# Sheet1.net
KiCad netlist of a schematic drawn in Altium Designer
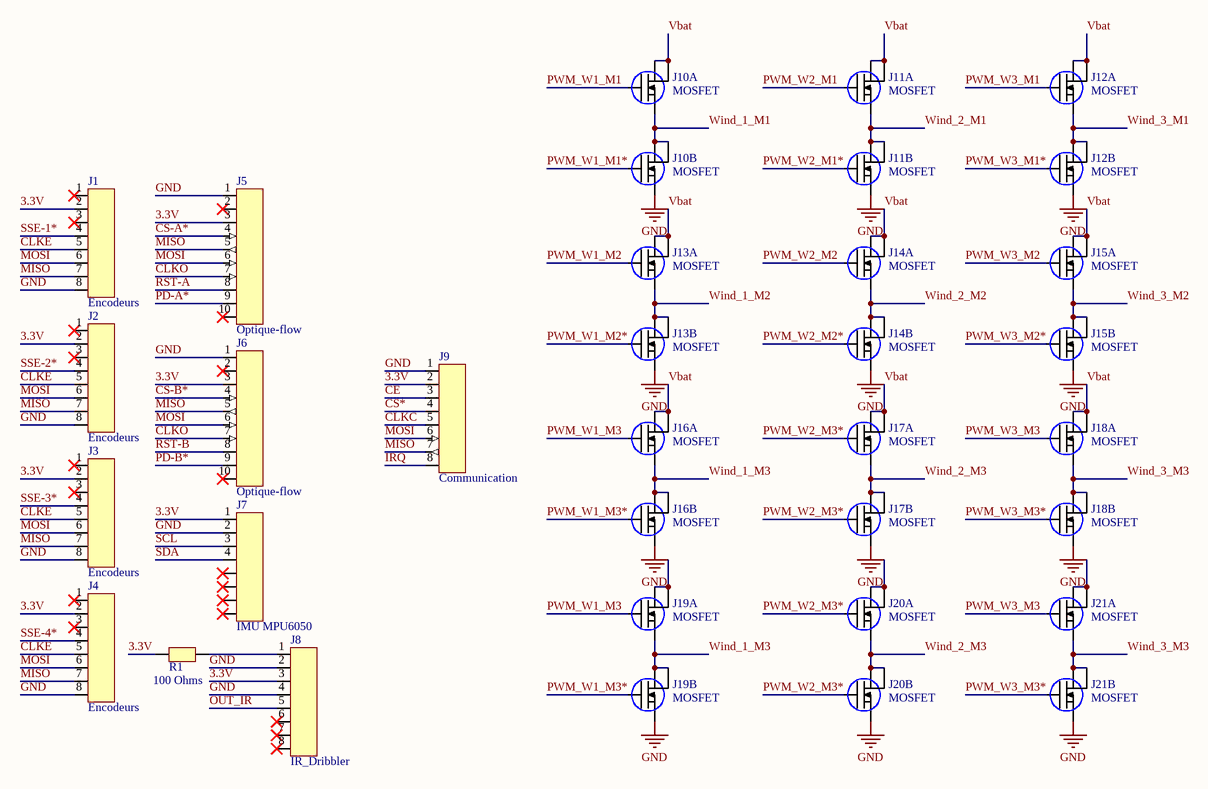
[diagram p0: Sheet1.SchDoc]

(export (version "E")
  (design (tool "Eeschema 10.0.6"))
  (components
    (comp (ref "J1")
      (value "Encodeurs")
      (footprint "Encodeur/IMU")
      (description "AS5048A")
      (libsource (lib "Schlib1") (part "Encodeurs"))
    )
    (comp (ref "J2")
      (value "Encodeurs")
      (footprint "Encodeur/IMU")
      (description "AS5048A")
      (libsource (lib "Schlib1") (part "Encodeurs"))
    )
    (comp (ref "J3")
      (value "Encodeurs")
      (footprint "Encodeur/IMU")
      (description "AS5048A")
      (libsource (lib "Schlib1") (part "Encodeurs"))
    )
    (comp (ref "J4")
      (value "Encodeurs")
      (footprint "Encodeur/IMU")
      (description "AS5048A")
      (libsource (lib "Schlib1") (part "Encodeurs"))
    )
    (comp (ref "J5")
      (value "Optique-flow")
      (footprint "IR_optique")
      (description "ADNS3080")
      (libsource (lib "Schlib1") (part "Optique-flow"))
    )
    (comp (ref "J6")
      (value "Optique-flow")
      (footprint "IR_optique")
      (description "ADNS3080")
      (libsource (lib "Schlib1") (part "Optique-flow"))
    )
    (comp (ref "J7")
      (value "IMU MPU6050")
      (footprint "Encodeur/IMU")
      (description "MPU6050 IMU")
      (libsource (lib "Schlib1") (part "IMU MPU6050"))
    )
    (comp (ref "J8")
      (value "IR_Dribbler")
      (footprint "Encodeur/IMU")
      (description "AS5048A")
      (libsource (lib "Schlib1") (part "Encodeurs"))
    )
    (comp (ref "J9")
      (value "Communication")
      (footprint "Comm nRF24L01")
      (description "Communication radio")
      (libsource (lib "Schlib1") (part "Communication"))
    )
    (comp (ref "J10")
      (value "MOSFET")
      (footprint "MOSFET")
      (description "MOSFET ESC IRF7910 10 A")
      (libsource (lib "Schlib1") (part "MOSFET"))
    )
    (comp (ref "J11")
      (value "MOSFET")
      (footprint "MOSFET")
      (description "MOSFET ESC IRF7910 10 A")
      (libsource (lib "Schlib1") (part "MOSFET"))
    )
    (comp (ref "J12")
      (value "MOSFET")
      (footprint "MOSFET")
      (description "MOSFET ESC IRF7910 10 A")
      (libsource (lib "Schlib1") (part "MOSFET"))
    )
    (comp (ref "J13")
      (value "MOSFET")
      (footprint "MOSFET")
      (description "MOSFET ESC IRF7910 10 A")
      (libsource (lib "Schlib1") (part "MOSFET"))
    )
    (comp (ref "J14")
      (value "MOSFET")
      (footprint "MOSFET")
      (description "MOSFET ESC IRF7910 10 A")
      (libsource (lib "Schlib1") (part "MOSFET"))
    )
    (comp (ref "J15")
      (value "MOSFET")
      (footprint "MOSFET")
      (description "MOSFET ESC IRF7910 10 A")
      (libsource (lib "Schlib1") (part "MOSFET"))
    )
    (comp (ref "J16")
      (value "MOSFET")
      (footprint "MOSFET")
      (description "MOSFET ESC IRF7910 10 A")
      (libsource (lib "Schlib1") (part "MOSFET"))
    )
    (comp (ref "J17")
      (value "MOSFET")
      (footprint "MOSFET")
      (description "MOSFET ESC IRF7910 10 A")
      (libsource (lib "Schlib1") (part "MOSFET"))
    )
    (comp (ref "J18")
      (value "MOSFET")
      (footprint "MOSFET")
      (description "MOSFET ESC IRF7910 10 A")
      (libsource (lib "Schlib1") (part "MOSFET"))
    )
    (comp (ref "J19")
      (value "MOSFET")
      (footprint "MOSFET")
      (description "MOSFET ESC IRF7910 10 A")
      (libsource (lib "Schlib1") (part "MOSFET"))
    )
    (comp (ref "J20")
      (value "MOSFET")
      (footprint "MOSFET")
      (description "MOSFET ESC IRF7910 10 A")
      (libsource (lib "Schlib1") (part "MOSFET"))
    )
    (comp (ref "J21")
      (value "MOSFET")
      (footprint "MOSFET")
      (description "MOSFET ESC IRF7910 10 A")
      (libsource (lib "Schlib1") (part "MOSFET"))
    )
    (comp (ref "R1")
      (value "Resistance")
      (footprint "empreinte 1206")
      (fields (field (name "100 OHMS") "100 Ohms"))
      (libsource (lib "Schlib1") (part "Resistance"))
    )
  )
  (nets
    (net (code "1") (name "/3.3V") (class "Default")
      (node (ref "J1") (pin "2") (pinfunction "2_2") (pintype "power_in"))
      (node (ref "J2") (pin "2") (pinfunction "2_2") (pintype "power_in"))
      (node (ref "J3") (pin "2") (pinfunction "2_2") (pintype "power_in"))
      (node (ref "J4") (pin "2") (pinfunction "2_2") (pintype "power_in"))
      (node (ref "J5") (pin "3") (pinfunction "3_3") (pintype "power_in"))
      (node (ref "J6") (pin "3") (pinfunction "3_3") (pintype "power_in"))
      (node (ref "J7") (pin "1") (pinfunction "1_1") (pintype "power_in"))
      (node (ref "J8") (pin "3") (pinfunction "3_3") (pintype "passive"))
      (node (ref "J9") (pin "2") (pinfunction "2_2") (pintype "power_in"))
      (node (ref "R1") (pin "1") (pinfunction "1_1") (pintype "passive"))
    )
    (net (code "2") (name "/CE") (class "Default")
      (node (ref "J9") (pin "3") (pinfunction "3_3") (pintype "passive"))
    )
    (net (code "3") (name "/CLKC") (class "Default")
      (node (ref "J9") (pin "5") (pinfunction "5_5") (pintype "passive"))
    )
    (net (code "4") (name "/CLKE") (class "Default")
      (node (ref "J1") (pin "5") (pinfunction "5_5") (pintype "passive"))
      (node (ref "J2") (pin "5") (pinfunction "5_5") (pintype "passive"))
      (node (ref "J3") (pin "5") (pinfunction "5_5") (pintype "passive"))
      (node (ref "J4") (pin "5") (pinfunction "5_5") (pintype "passive"))
    )
    (net (code "5") (name "/CLKO") (class "Default")
      (node (ref "J5") (pin "7") (pinfunction "7_7") (pintype "input"))
      (node (ref "J6") (pin "7") (pinfunction "7_7") (pintype "input"))
    )
    (net (code "6") (name "/CS*") (class "Default")
      (node (ref "J9") (pin "4") (pinfunction "4_4") (pintype "passive"))
    )
    (net (code "7") (name "/CS-A*") (class "Default")
      (node (ref "J5") (pin "4") (pinfunction "4_4") (pintype "input"))
    )
    (net (code "8") (name "/CS-B*") (class "Default")
      (node (ref "J6") (pin "4") (pinfunction "4_4") (pintype "input"))
    )
    (net (code "9") (name "/IRQ") (class "Default")
      (node (ref "J9") (pin "8") (pinfunction "8_8") (pintype "passive"))
    )
    (net (code "10") (name "/MISO") (class "Default")
      (node (ref "J1") (pin "7") (pinfunction "7_7") (pintype "passive"))
      (node (ref "J2") (pin "7") (pinfunction "7_7") (pintype "passive"))
      (node (ref "J3") (pin "7") (pinfunction "7_7") (pintype "passive"))
      (node (ref "J4") (pin "7") (pinfunction "7_7") (pintype "passive"))
      (node (ref "J5") (pin "5") (pinfunction "5_5") (pintype "output"))
      (node (ref "J6") (pin "5") (pinfunction "5_5") (pintype "output"))
      (node (ref "J9") (pin "7") (pinfunction "7_7") (pintype "output"))
    )
    (net (code "11") (name "/MOSI") (class "Default")
      (node (ref "J1") (pin "6") (pinfunction "6_6") (pintype "passive"))
      (node (ref "J2") (pin "6") (pinfunction "6_6") (pintype "passive"))
      (node (ref "J3") (pin "6") (pinfunction "6_6") (pintype "passive"))
      (node (ref "J4") (pin "6") (pinfunction "6_6") (pintype "passive"))
      (node (ref "J5") (pin "6") (pinfunction "6_6") (pintype "input"))
      (node (ref "J6") (pin "6") (pinfunction "6_6") (pintype "input"))
      (node (ref "J9") (pin "6") (pinfunction "6_6") (pintype "input"))
    )
    (net (code "12") (name "/OUT_IR") (class "Default")
      (node (ref "J8") (pin "5") (pinfunction "5_5") (pintype "passive"))
    )
    (net (code "13") (name "/PD-A*") (class "Default")
      (node (ref "J5") (pin "9") (pinfunction "9_9") (pintype "passive"))
    )
    (net (code "14") (name "/PD-B*") (class "Default")
      (node (ref "J6") (pin "9") (pinfunction "9_9") (pintype "passive"))
    )
    (net (code "15") (name "/PWM_W1_M1") (class "Default")
      (node (ref "J10") (pin "2") (pinfunction "2_2") (pintype "passive"))
    )
    (net (code "16") (name "/PWM_W1_M1*") (class "Default")
      (node (ref "J10") (pin "4") (pinfunction "4_4") (pintype "passive"))
    )
    (net (code "17") (name "/PWM_W1_M2") (class "Default")
      (node (ref "J13") (pin "2") (pinfunction "2_2") (pintype "passive"))
    )
    (net (code "18") (name "/PWM_W1_M2*") (class "Default")
      (node (ref "J13") (pin "4") (pinfunction "4_4") (pintype "passive"))
    )
    (net (code "19") (name "/PWM_W1_M3") (class "Default")
      (node (ref "J16") (pin "2") (pinfunction "2_2") (pintype "passive"))
      (node (ref "J19") (pin "2") (pinfunction "2_2") (pintype "passive"))
    )
    (net (code "20") (name "/PWM_W1_M3*") (class "Default")
      (node (ref "J16") (pin "4") (pinfunction "4_4") (pintype "passive"))
      (node (ref "J19") (pin "4") (pinfunction "4_4") (pintype "passive"))
    )
    (net (code "21") (name "/PWM_W2_M1") (class "Default")
      (node (ref "J11") (pin "2") (pinfunction "2_2") (pintype "passive"))
    )
    (net (code "22") (name "/PWM_W2_M1*") (class "Default")
      (node (ref "J11") (pin "4") (pinfunction "4_4") (pintype "passive"))
    )
    (net (code "23") (name "/PWM_W2_M2") (class "Default")
      (node (ref "J14") (pin "2") (pinfunction "2_2") (pintype "passive"))
    )
    (net (code "24") (name "/PWM_W2_M2*") (class "Default")
      (node (ref "J14") (pin "4") (pinfunction "4_4") (pintype "passive"))
    )
    (net (code "25") (name "/PWM_W2_M3*") (class "Default")
      (node (ref "J17") (pin "2") (pinfunction "2_2") (pintype "passive"))
      (node (ref "J17") (pin "4") (pinfunction "4_4") (pintype "passive"))
      (node (ref "J20") (pin "2") (pinfunction "2_2") (pintype "passive"))
      (node (ref "J20") (pin "4") (pinfunction "4_4") (pintype "passive"))
    )
    (net (code "26") (name "/PWM_W3_M1") (class "Default")
      (node (ref "J12") (pin "2") (pinfunction "2_2") (pintype "passive"))
    )
    (net (code "27") (name "/PWM_W3_M1*") (class "Default")
      (node (ref "J12") (pin "4") (pinfunction "4_4") (pintype "passive"))
    )
    (net (code "28") (name "/PWM_W3_M2") (class "Default")
      (node (ref "J15") (pin "2") (pinfunction "2_2") (pintype "passive"))
    )
    (net (code "29") (name "/PWM_W3_M2*") (class "Default")
      (node (ref "J15") (pin "4") (pinfunction "4_4") (pintype "passive"))
    )
    (net (code "30") (name "/PWM_W3_M3") (class "Default")
      (node (ref "J18") (pin "2") (pinfunction "2_2") (pintype "passive"))
      (node (ref "J21") (pin "2") (pinfunction "2_2") (pintype "passive"))
    )
    (net (code "31") (name "/PWM_W3_M3*") (class "Default")
      (node (ref "J18") (pin "4") (pinfunction "4_4") (pintype "passive"))
      (node (ref "J21") (pin "4") (pinfunction "4_4") (pintype "passive"))
    )
    (net (code "32") (name "/RST-A") (class "Default")
      (node (ref "J5") (pin "8") (pinfunction "8_8") (pintype "passive"))
    )
    (net (code "33") (name "/RST-B") (class "Default")
      (node (ref "J6") (pin "8") (pinfunction "8_8") (pintype "passive"))
    )
    (net (code "34") (name "/SCL") (class "Default")
      (node (ref "J7") (pin "3") (pinfunction "3_3") (pintype "passive"))
    )
    (net (code "35") (name "/SDA") (class "Default")
      (node (ref "J7") (pin "4") (pinfunction "4_4") (pintype "bidirectional"))
    )
    (net (code "36") (name "/SSE-1*") (class "Default")
      (node (ref "J1") (pin "4") (pinfunction "4_4") (pintype "passive"))
    )
    (net (code "37") (name "/SSE-2*") (class "Default")
      (node (ref "J2") (pin "4") (pinfunction "4_4") (pintype "passive"))
    )
    (net (code "38") (name "/SSE-3*") (class "Default")
      (node (ref "J3") (pin "4") (pinfunction "4_4") (pintype "passive"))
    )
    (net (code "39") (name "/SSE-4*") (class "Default")
      (node (ref "J4") (pin "4") (pinfunction "4_4") (pintype "passive"))
    )
    (net (code "40") (name "/Vbat") (class "Default")
      (node (ref "J10") (pin "7") (pinfunction "7_7") (pintype "passive"))
      (node (ref "J10") (pin "8") (pinfunction "8_8") (pintype "passive"))
      (node (ref "J11") (pin "7") (pinfunction "7_7") (pintype "passive"))
      (node (ref "J11") (pin "8") (pinfunction "8_8") (pintype "passive"))
      (node (ref "J12") (pin "7") (pinfunction "7_7") (pintype "passive"))
      (node (ref "J12") (pin "8") (pinfunction "8_8") (pintype "passive"))
      (node (ref "J13") (pin "7") (pinfunction "7_7") (pintype "passive"))
      (node (ref "J13") (pin "8") (pinfunction "8_8") (pintype "passive"))
      (node (ref "J14") (pin "7") (pinfunction "7_7") (pintype "passive"))
      (node (ref "J14") (pin "8") (pinfunction "8_8") (pintype "passive"))
      (node (ref "J15") (pin "7") (pinfunction "7_7") (pintype "passive"))
      (node (ref "J15") (pin "8") (pinfunction "8_8") (pintype "passive"))
      (node (ref "J16") (pin "7") (pinfunction "7_7") (pintype "passive"))
      (node (ref "J16") (pin "8") (pinfunction "8_8") (pintype "passive"))
      (node (ref "J17") (pin "7") (pinfunction "7_7") (pintype "passive"))
      (node (ref "J17") (pin "8") (pinfunction "8_8") (pintype "passive"))
      (node (ref "J18") (pin "7") (pinfunction "7_7") (pintype "passive"))
      (node (ref "J18") (pin "8") (pinfunction "8_8") (pintype "passive"))
    )
    (net (code "41") (name "/Wind_1_M1") (class "Default")
      (node (ref "J10") (pin "1") (pinfunction "1_1") (pintype "passive"))
      (node (ref "J10") (pin "5") (pinfunction "5_5") (pintype "passive"))
      (node (ref "J10") (pin "6") (pinfunction "6_6") (pintype "passive"))
    )
    (net (code "42") (name "/Wind_1_M2") (class "Default")
      (node (ref "J13") (pin "1") (pinfunction "1_1") (pintype "passive"))
      (node (ref "J13") (pin "5") (pinfunction "5_5") (pintype "passive"))
      (node (ref "J13") (pin "6") (pinfunction "6_6") (pintype "passive"))
    )
    (net (code "43") (name "/Wind_1_M3") (class "Default")
      (node (ref "J16") (pin "1") (pinfunction "1_1") (pintype "passive"))
      (node (ref "J16") (pin "5") (pinfunction "5_5") (pintype "passive"))
      (node (ref "J16") (pin "6") (pinfunction "6_6") (pintype "passive"))
      (node (ref "J19") (pin "1") (pinfunction "1_1") (pintype "passive"))
      (node (ref "J19") (pin "5") (pinfunction "5_5") (pintype "passive"))
      (node (ref "J19") (pin "6") (pinfunction "6_6") (pintype "passive"))
    )
    (net (code "44") (name "/Wind_2_M1") (class "Default")
      (node (ref "J11") (pin "1") (pinfunction "1_1") (pintype "passive"))
      (node (ref "J11") (pin "5") (pinfunction "5_5") (pintype "passive"))
      (node (ref "J11") (pin "6") (pinfunction "6_6") (pintype "passive"))
    )
    (net (code "45") (name "/Wind_2_M2") (class "Default")
      (node (ref "J14") (pin "1") (pinfunction "1_1") (pintype "passive"))
      (node (ref "J14") (pin "5") (pinfunction "5_5") (pintype "passive"))
      (node (ref "J14") (pin "6") (pinfunction "6_6") (pintype "passive"))
    )
    (net (code "46") (name "/Wind_2_M3") (class "Default")
      (node (ref "J17") (pin "1") (pinfunction "1_1") (pintype "passive"))
      (node (ref "J17") (pin "5") (pinfunction "5_5") (pintype "passive"))
      (node (ref "J17") (pin "6") (pinfunction "6_6") (pintype "passive"))
      (node (ref "J20") (pin "1") (pinfunction "1_1") (pintype "passive"))
      (node (ref "J20") (pin "5") (pinfunction "5_5") (pintype "passive"))
      (node (ref "J20") (pin "6") (pinfunction "6_6") (pintype "passive"))
    )
    (net (code "47") (name "/Wind_3_M1") (class "Default")
      (node (ref "J12") (pin "1") (pinfunction "1_1") (pintype "passive"))
      (node (ref "J12") (pin "5") (pinfunction "5_5") (pintype "passive"))
      (node (ref "J12") (pin "6") (pinfunction "6_6") (pintype "passive"))
    )
    (net (code "48") (name "/Wind_3_M2") (class "Default")
      (node (ref "J15") (pin "1") (pinfunction "1_1") (pintype "passive"))
      (node (ref "J15") (pin "5") (pinfunction "5_5") (pintype "passive"))
      (node (ref "J15") (pin "6") (pinfunction "6_6") (pintype "passive"))
    )
    (net (code "49") (name "/Wind_3_M3") (class "Default")
      (node (ref "J18") (pin "1") (pinfunction "1_1") (pintype "passive"))
      (node (ref "J18") (pin "5") (pinfunction "5_5") (pintype "passive"))
      (node (ref "J18") (pin "6") (pinfunction "6_6") (pintype "passive"))
      (node (ref "J21") (pin "1") (pinfunction "1_1") (pintype "passive"))
      (node (ref "J21") (pin "5") (pinfunction "5_5") (pintype "passive"))
      (node (ref "J21") (pin "6") (pinfunction "6_6") (pintype "passive"))
    )
    (net (code "50") (name "GND") (class "Default")
      (node (ref "J1") (pin "8") (pinfunction "8_8") (pintype "power_in"))
      (node (ref "J10") (pin "3") (pinfunction "3_3") (pintype "passive"))
      (node (ref "J11") (pin "3") (pinfunction "3_3") (pintype "passive"))
      (node (ref "J12") (pin "3") (pinfunction "3_3") (pintype "passive"))
      (node (ref "J13") (pin "3") (pinfunction "3_3") (pintype "passive"))
      (node (ref "J14") (pin "3") (pinfunction "3_3") (pintype "passive"))
      (node (ref "J15") (pin "3") (pinfunction "3_3") (pintype "passive"))
      (node (ref "J16") (pin "3") (pinfunction "3_3") (pintype "passive"))
      (node (ref "J17") (pin "3") (pinfunction "3_3") (pintype "passive"))
      (node (ref "J18") (pin "3") (pinfunction "3_3") (pintype "passive"))
      (node (ref "J19") (pin "3") (pinfunction "3_3") (pintype "passive"))
      (node (ref "J2") (pin "8") (pinfunction "8_8") (pintype "power_in"))
      (node (ref "J20") (pin "3") (pinfunction "3_3") (pintype "passive"))
      (node (ref "J21") (pin "3") (pinfunction "3_3") (pintype "passive"))
      (node (ref "J3") (pin "8") (pinfunction "8_8") (pintype "power_in"))
      (node (ref "J4") (pin "8") (pinfunction "8_8") (pintype "power_in"))
      (node (ref "J5") (pin "1") (pinfunction "1_1") (pintype "power_in"))
      (node (ref "J6") (pin "1") (pinfunction "1_1") (pintype "power_in"))
      (node (ref "J7") (pin "2") (pinfunction "2_2") (pintype "power_in"))
      (node (ref "J8") (pin "2") (pinfunction "2_2") (pintype "power_in"))
      (node (ref "J8") (pin "4") (pinfunction "4_4") (pintype "passive"))
      (node (ref "J9") (pin "1") (pinfunction "1_1") (pintype "power_in"))
    )
    (net (code "51") (name "Net-(J8-Pad1)") (class "Default")
      (node (ref "J8") (pin "1") (pinfunction "1_1") (pintype "power_in"))
      (node (ref "R1") (pin "2") (pinfunction "2_2") (pintype "passive"))
    )
    (net (code "52") (name "Net-(J19-Pad7)") (class "Default")
      (node (ref "J19") (pin "7") (pinfunction "7_7") (pintype "passive"))
      (node (ref "J19") (pin "8") (pinfunction "8_8") (pintype "passive"))
    )
    (net (code "53") (name "Net-(J20-Pad7)") (class "Default")
      (node (ref "J20") (pin "7") (pinfunction "7_7") (pintype "passive"))
      (node (ref "J20") (pin "8") (pinfunction "8_8") (pintype "passive"))
    )
    (net (code "54") (name "Net-(J21-Pad7)") (class "Default")
      (node (ref "J21") (pin "7") (pinfunction "7_7") (pintype "passive"))
      (node (ref "J21") (pin "8") (pinfunction "8_8") (pintype "passive"))
    )
    (net (code "55") (name "unconnected-(J1-Pad1)") (class "Default")
      (node (ref "J1") (pin "1") (pinfunction "1_1") (pintype "power_in+no_connect"))
    )
    (net (code "56") (name "unconnected-(J1-Pad3)") (class "Default")
      (node (ref "J1") (pin "3") (pinfunction "3_3") (pintype "passive+no_connect"))
    )
    (net (code "57") (name "unconnected-(J2-Pad1)") (class "Default")
      (node (ref "J2") (pin "1") (pinfunction "1_1") (pintype "power_in+no_connect"))
    )
    (net (code "58") (name "unconnected-(J2-Pad3)") (class "Default")
      (node (ref "J2") (pin "3") (pinfunction "3_3") (pintype "passive+no_connect"))
    )
    (net (code "59") (name "unconnected-(J3-Pad1)") (class "Default")
      (node (ref "J3") (pin "1") (pinfunction "1_1") (pintype "power_in+no_connect"))
    )
    (net (code "60") (name "unconnected-(J3-Pad3)") (class "Default")
      (node (ref "J3") (pin "3") (pinfunction "3_3") (pintype "passive+no_connect"))
    )
    (net (code "61") (name "unconnected-(J4-Pad1)") (class "Default")
      (node (ref "J4") (pin "1") (pinfunction "1_1") (pintype "power_in+no_connect"))
    )
    (net (code "62") (name "unconnected-(J4-Pad3)") (class "Default")
      (node (ref "J4") (pin "3") (pinfunction "3_3") (pintype "passive+no_connect"))
    )
    (net (code "63") (name "unconnected-(J5-Pad2)") (class "Default")
      (node (ref "J5") (pin "2") (pinfunction "2_2") (pintype "power_in+no_connect"))
    )
    (net (code "64") (name "unconnected-(J5-Pad10)") (class "Default")
      (node (ref "J5") (pin "10") (pinfunction "10_10") (pintype "passive+no_connect"))
    )
    (net (code "65") (name "unconnected-(J6-Pad2)") (class "Default")
      (node (ref "J6") (pin "2") (pinfunction "2_2") (pintype "power_in+no_connect"))
    )
    (net (code "66") (name "unconnected-(J6-Pad10)") (class "Default")
      (node (ref "J6") (pin "10") (pinfunction "10_10") (pintype "passive+no_connect"))
    )
    (net (code "67") (name "unconnected-(J7-Pad5)") (class "Default")
      (node (ref "J7") (pin "5") (pinfunction "5_5") (pintype "passive+no_connect"))
    )
    (net (code "68") (name "unconnected-(J7-Pad6)") (class "Default")
      (node (ref "J7") (pin "6") (pinfunction "6_6") (pintype "passive+no_connect"))
    )
    (net (code "69") (name "unconnected-(J7-Pad7)") (class "Default")
      (node (ref "J7") (pin "7") (pinfunction "7_7") (pintype "passive+no_connect"))
    )
    (net (code "70") (name "unconnected-(J7-Pad8)") (class "Default")
      (node (ref "J7") (pin "8") (pinfunction "8_8") (pintype "passive+no_connect"))
    )
    (net (code "71") (name "unconnected-(J8-Pad6)") (class "Default")
      (node (ref "J8") (pin "6") (pinfunction "6_6") (pintype "passive+no_connect"))
    )
    (net (code "72") (name "unconnected-(J8-Pad7)") (class "Default")
      (node (ref "J8") (pin "7") (pinfunction "7_7") (pintype "passive+no_connect"))
    )
    (net (code "73") (name "unconnected-(J8-Pad8)") (class "Default")
      (node (ref "J8") (pin "8") (pinfunction "8_8") (pintype "power_in+no_connect"))
    )
  )
)
